# ASM2001.net
KiCad netlist of a schematic drawn in EAGLE
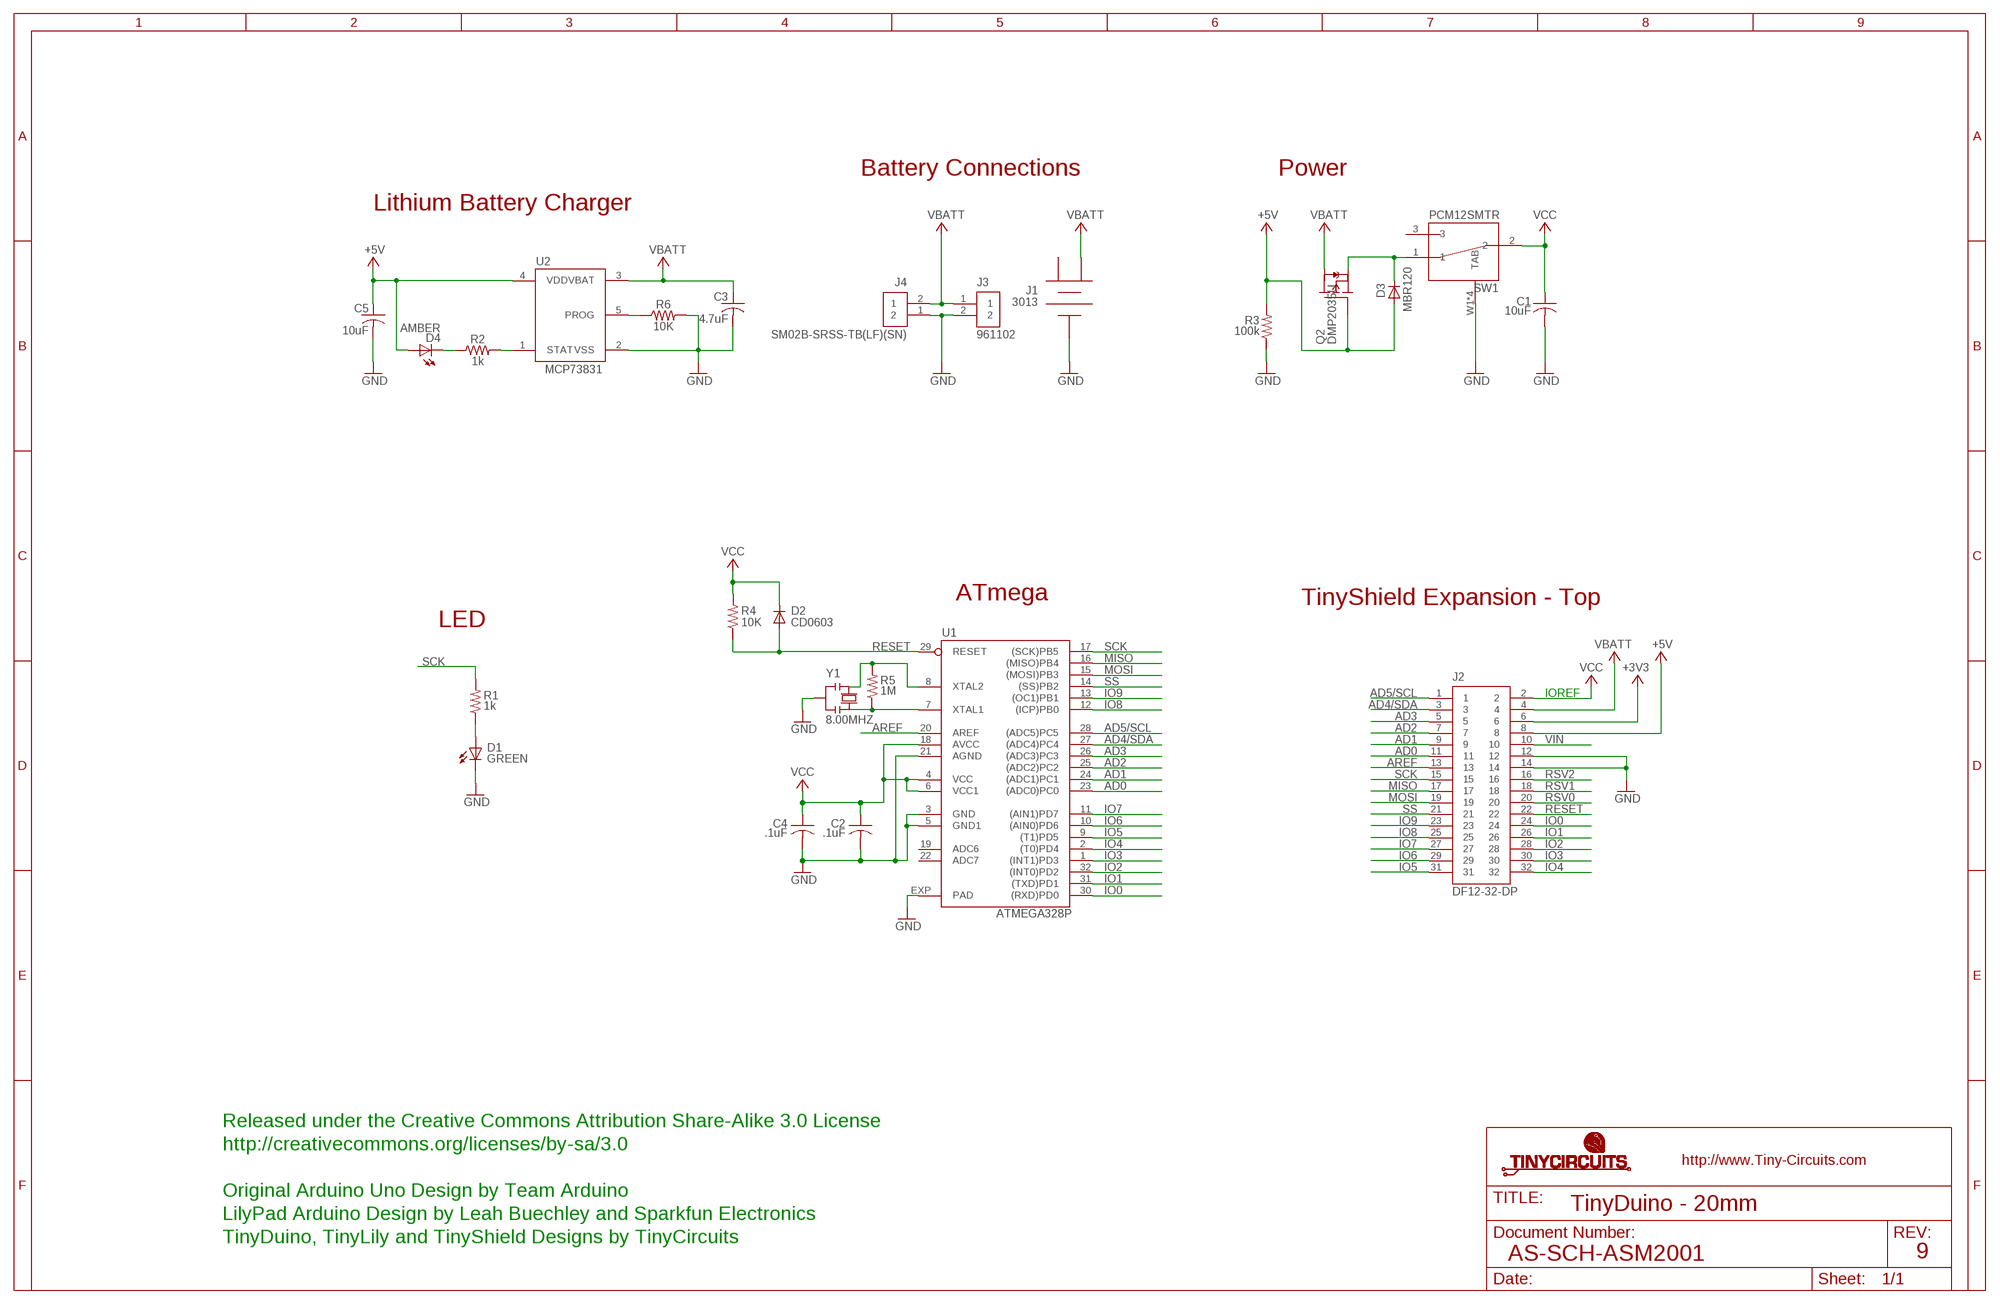
[diagram p0: schematic, sheet 1]

(export (version "E")
  (design (tool "Eeschema 10.0.6"))
  (components
    (comp (ref "C1")
      (value "10uF")
      (footprint "eagle-import:C0603")
      (fields (field (name "PARTNO") "AS-ITM-00002") (field (name "PARTNO_1") "AS-ITM-00002"))
      (libsource (lib "eagle-import") (part "AS-ITM-00002"))
    )
    (comp (ref "C2")
      (value ".1uF")
      (footprint "eagle-import:C0402")
      (fields (field (name "PARTNO") "AS-ITM-00008") (field (name "PARTNO_1") "AS-ITM-00008"))
      (libsource (lib "eagle-import") (part "AS-ITM-00008"))
    )
    (comp (ref "C3")
      (value "4.7uF")
      (footprint "eagle-import:C0402")
      (fields (field (name "PARTNO") "AS-ITM-00242") (field (name "PARTNO_1") "AS-ITM-00242"))
      (libsource (lib "eagle-import") (part "AS-ITM-00242"))
    )
    (comp (ref "C4")
      (value ".1uF")
      (footprint "eagle-import:C0402")
      (fields (field (name "PARTNO") "AS-ITM-00008") (field (name "PARTNO_1") "AS-ITM-00008"))
      (libsource (lib "eagle-import") (part "AS-ITM-00008"))
    )
    (comp (ref "C5")
      (value "10uF")
      (footprint "eagle-import:C0603")
      (fields (field (name "PARTNO") "AS-ITM-00002") (field (name "PARTNO_1") "AS-ITM-00002"))
      (libsource (lib "eagle-import") (part "AS-ITM-00002"))
    )
    (comp (ref "D1")
      (value "GREEN")
      (footprint "eagle-import:LNJ_LED")
      (fields (field (name "PARTNO") "AS-ITM-00011") (field (name "PARTNO_1") "AS-ITM-00011"))
      (libsource (lib "eagle-import") (part "AS-ITM-00011"))
    )
    (comp (ref "D2")
      (value "CD0603")
      (footprint "eagle-import:0603")
      (fields (field (name "PARTNO") "AS-ITM-00009") (field (name "PARTNO_1") "AS-ITM-00009"))
      (libsource (lib "eagle-import") (part "AS-ITM-00009"))
    )
    (comp (ref "D3")
      (value "MBR120")
      (footprint "eagle-import:SOD-123FL")
      (fields (field (name "PARTNO") "AS-ITM-00111"))
      (libsource (lib "eagle-import") (part "AS-ITM-00111"))
    )
    (comp (ref "D4")
      (value "AMBER")
      (footprint "eagle-import:LNJ_LED")
      (fields (field (name "PARTNO") "AS-ITM-00026") (field (name "PARTNO_1") "AS-ITM-00026"))
      (libsource (lib "eagle-import") (part "AS-ITM-00026"))
    )
    (comp (ref "J1")
      (value "3013")
      (footprint "eagle-import:3013")
      (fields (field (name "PARTNO") "AS-ITM-00001") (field (name "PARTNO_1") "AS-ITM-00001"))
      (libsource (lib "eagle-import") (part "AS-ITM-00001"))
    )
    (comp (ref "J2")
      (value "DF12-32-DP")
      (footprint "eagle-import:DF12-32-DP")
      (fields (field (name "PARTNO") "AS-ITM-00015") (field (name "PARTNO_1") "AS-ITM-00015"))
      (libsource (lib "eagle-import") (part "AS-ITM-00015"))
    )
    (comp (ref "J3")
      (value "961102")
      (footprint "eagle-import:2X.1_")
      (fields (field (name "PARTNO") "AS-ITM-00044"))
      (libsource (lib "eagle-import") (part "AS-ITM-00044"))
    )
    (comp (ref "J4")
      (value "SM02B-SRSS-TB(LF)(SN)")
      (footprint "eagle-import:JST_SH_2X1")
      (fields (field (name "PARTNO") "AS-ITM-00231"))
      (libsource (lib "eagle-import") (part "AS-ITM-00231"))
    )
    (comp (ref "Q2")
      (value "DMP2035U")
      (footprint "eagle-import:SOT23")
      (fields (field (name "PARTNO") "AS-ITM-00024"))
      (libsource (lib "eagle-import") (part "AS-ITM-00024"))
    )
    (comp (ref "R1")
      (value "1k")
      (footprint "eagle-import:0402")
      (fields (field (name "PARTNO") "AS-ITM-00003") (field (name "PARTNO_1") "AS-ITM-00003"))
      (libsource (lib "eagle-import") (part "AS-ITM-00003"))
    )
    (comp (ref "R2")
      (value "1k")
      (footprint "eagle-import:0402")
      (fields (field (name "PARTNO") "AS-ITM-00003") (field (name "PARTNO_1") "AS-ITM-00003"))
      (libsource (lib "eagle-import") (part "AS-ITM-00003"))
    )
    (comp (ref "R3")
      (value "100k")
      (footprint "eagle-import:0402")
      (fields (field (name "PARTNO") "AS-ITM-00004") (field (name "PARTNO_1") "AS-ITM-00004"))
      (libsource (lib "eagle-import") (part "AS-ITM-00004"))
    )
    (comp (ref "R4")
      (value "10K")
      (footprint "eagle-import:0402")
      (fields (field (name "PARTNO") "AS-ITM-00032") (field (name "PARTNO_1") "AS-ITM-00032"))
      (libsource (lib "eagle-import") (part "AS-ITM-00032"))
    )
    (comp (ref "R5")
      (value "1M")
      (footprint "eagle-import:0402")
      (fields (field (name "PARTNO") "AS-ITM-00005") (field (name "PARTNO_1") "AS-ITM-00005"))
      (libsource (lib "eagle-import") (part "AS-ITM-00005"))
    )
    (comp (ref "R6")
      (value "10K")
      (footprint "eagle-import:0402")
      (fields (field (name "PARTNO") "AS-ITM-00032"))
      (libsource (lib "eagle-import") (part "AS-ITM-00032"))
    )
    (comp (ref "SW1")
      (value "PCM12SMTR")
      (footprint "eagle-import:PCM12SMTR")
      (fields (field (name "PARTNO") "AS-ITM-00220"))
      (libsource (lib "eagle-import") (part "AS-ITM-00220"))
    )
    (comp (ref "U1")
      (value "ATMEGA328P")
      (footprint "eagle-import:ATMEL_QFN32")
      (fields (field (name "PARTNO") "AS-ITM-00013") (field (name "PARTNO_1") "AS-ITM-00013"))
      (libsource (lib "eagle-import") (part "AS-ITM-00013MU"))
    )
    (comp (ref "U2")
      (value "MCP73831")
      (footprint "eagle-import:SOT-23")
      (fields (field (name "PARTNO") "AS-ITM-00136"))
      (libsource (lib "eagle-import") (part "AS-ITM-00136"))
    )
    (comp (ref "Y1")
      (value "8.00MHZ")
      (footprint "eagle-import:RESONATOR_SMALL")
      (fields (field (name "PARTNO") "AS-ITM-0027") (field (name "PARTNO_1") "AS-ITM-00027"))
      (libsource (lib "eagle-import") (part "AS-ITM-00027B"))
    )
  )
  (nets
    (net (code "1") (name "+3V3") (class "Default")
      (node (ref "J2") (pin "6") (pinfunction "6_6") (pintype "bidirectional"))
    )
    (net (code "2") (name "+5V") (class "Default")
      (node (ref "C5") (pin "1") (pinfunction "1_1") (pintype "passive"))
      (node (ref "D3") (pin "A") (pinfunction "A_A") (pintype "passive"))
      (node (ref "D4") (pin "A") (pinfunction "A_A") (pintype "passive"))
      (node (ref "J2") (pin "8") (pinfunction "8_8") (pintype "bidirectional"))
      (node (ref "Q2") (pin "B") (pinfunction "G_B") (pintype "passive"))
      (node (ref "R3") (pin "2") (pinfunction "2_2") (pintype "passive"))
      (node (ref "U2") (pin "4") (pinfunction "VDD_4") (pintype "bidirectional"))
    )
    (net (code "3") (name "/1") (class "Default")
      (node (ref "J1") (pin "1") (pinfunction "1_1") (pintype "power_in"))
    )
    (net (code "4") (name "/AD0") (class "Default")
      (node (ref "J2") (pin "11") (pinfunction "11_11") (pintype "bidirectional"))
      (node (ref "U1") (pin "23") (pinfunction "(ADC0)PC0_23") (pintype "bidirectional"))
    )
    (net (code "5") (name "/AD1") (class "Default")
      (node (ref "J2") (pin "9") (pinfunction "9_9") (pintype "bidirectional"))
      (node (ref "U1") (pin "24") (pinfunction "(ADC1)PC1_24") (pintype "bidirectional"))
    )
    (net (code "6") (name "/AD2") (class "Default")
      (node (ref "J2") (pin "7") (pinfunction "7_7") (pintype "bidirectional"))
      (node (ref "U1") (pin "25") (pinfunction "(ADC2)PC2_25") (pintype "bidirectional"))
    )
    (net (code "7") (name "/AD3") (class "Default")
      (node (ref "J2") (pin "5") (pinfunction "5_5") (pintype "bidirectional"))
      (node (ref "U1") (pin "26") (pinfunction "(ADC3)PC3_26") (pintype "bidirectional"))
    )
    (net (code "8") (name "/AD4{slash}SDA") (class "Default")
      (node (ref "J2") (pin "3") (pinfunction "3_3") (pintype "bidirectional"))
      (node (ref "U1") (pin "27") (pinfunction "(ADC4)PC4_27") (pintype "bidirectional"))
    )
    (net (code "9") (name "/AD5{slash}SCL") (class "Default")
      (node (ref "J2") (pin "1") (pinfunction "1_1") (pintype "bidirectional"))
      (node (ref "U1") (pin "28") (pinfunction "(ADC5)PC5_28") (pintype "bidirectional"))
    )
    (net (code "10") (name "/AREF") (class "Default")
      (node (ref "J2") (pin "13") (pinfunction "13_13") (pintype "bidirectional"))
      (node (ref "U1") (pin "20") (pinfunction "AREF_20") (pintype "passive"))
    )
    (net (code "11") (name "/IO0") (class "Default")
      (node (ref "J2") (pin "24") (pinfunction "24_24") (pintype "bidirectional"))
      (node (ref "U1") (pin "30") (pinfunction "(RXD)PD0_30") (pintype "bidirectional"))
    )
    (net (code "12") (name "/IO1") (class "Default")
      (node (ref "J2") (pin "26") (pinfunction "26_26") (pintype "bidirectional"))
      (node (ref "U1") (pin "31") (pinfunction "(TXD)PD1_31") (pintype "bidirectional"))
    )
    (net (code "13") (name "/IO2") (class "Default")
      (node (ref "J2") (pin "28") (pinfunction "28_28") (pintype "bidirectional"))
      (node (ref "U1") (pin "32") (pinfunction "(INT0)PD2_32") (pintype "bidirectional"))
    )
    (net (code "14") (name "/IO3") (class "Default")
      (node (ref "J2") (pin "30") (pinfunction "30_30") (pintype "bidirectional"))
      (node (ref "U1") (pin "1") (pinfunction "(INT1)PD3_1") (pintype "bidirectional"))
    )
    (net (code "15") (name "/IO4") (class "Default")
      (node (ref "J2") (pin "32") (pinfunction "32_32") (pintype "bidirectional"))
      (node (ref "U1") (pin "2") (pinfunction "(T0)PD4_2") (pintype "bidirectional"))
    )
    (net (code "16") (name "/IO5") (class "Default")
      (node (ref "J2") (pin "31") (pinfunction "31_31") (pintype "bidirectional"))
      (node (ref "U1") (pin "9") (pinfunction "(T1)PD5_9") (pintype "bidirectional"))
    )
    (net (code "17") (name "/IO6") (class "Default")
      (node (ref "J2") (pin "29") (pinfunction "29_29") (pintype "bidirectional"))
      (node (ref "U1") (pin "10") (pinfunction "(AIN0)PD6_10") (pintype "bidirectional"))
    )
    (net (code "18") (name "/IO7") (class "Default")
      (node (ref "J2") (pin "27") (pinfunction "27_27") (pintype "bidirectional"))
      (node (ref "U1") (pin "11") (pinfunction "(AIN1)PD7_11") (pintype "bidirectional"))
    )
    (net (code "19") (name "/IO8") (class "Default")
      (node (ref "J2") (pin "25") (pinfunction "25_25") (pintype "bidirectional"))
      (node (ref "U1") (pin "12") (pinfunction "(ICP)PB0_12") (pintype "bidirectional"))
    )
    (net (code "20") (name "/IO9") (class "Default")
      (node (ref "J2") (pin "23") (pinfunction "23_23") (pintype "bidirectional"))
      (node (ref "U1") (pin "13") (pinfunction "(OC1)PB1_13") (pintype "bidirectional"))
    )
    (net (code "21") (name "/MISO") (class "Default")
      (node (ref "J2") (pin "17") (pinfunction "17_17") (pintype "bidirectional"))
      (node (ref "U1") (pin "16") (pinfunction "(MISO)PB4_16") (pintype "bidirectional"))
    )
    (net (code "22") (name "/MOSI") (class "Default")
      (node (ref "J2") (pin "19") (pinfunction "19_19") (pintype "bidirectional"))
      (node (ref "U1") (pin "15") (pinfunction "(MOSI)PB3_15") (pintype "bidirectional"))
    )
    (net (code "23") (name "/RESET") (class "Default")
      (node (ref "D2") (pin "A") (pinfunction "A_A") (pintype "passive"))
      (node (ref "J2") (pin "22") (pinfunction "22_22") (pintype "bidirectional"))
      (node (ref "R4") (pin "1") (pinfunction "1_1") (pintype "passive"))
      (node (ref "U1") (pin "29") (pinfunction "RESET_29") (pintype "input"))
    )
    (net (code "24") (name "/RSV0") (class "Default")
      (node (ref "J2") (pin "20") (pinfunction "20_20") (pintype "bidirectional"))
    )
    (net (code "25") (name "/RSV1") (class "Default")
      (node (ref "J2") (pin "18") (pinfunction "18_18") (pintype "bidirectional"))
    )
    (net (code "26") (name "/RSV2") (class "Default")
      (node (ref "J2") (pin "16") (pinfunction "16_16") (pintype "bidirectional"))
    )
    (net (code "27") (name "/SCK") (class "Default")
      (node (ref "J2") (pin "15") (pinfunction "15_15") (pintype "bidirectional"))
      (node (ref "R1") (pin "2") (pinfunction "2_2") (pintype "passive"))
      (node (ref "U1") (pin "17") (pinfunction "(SCK)PB5_17") (pintype "bidirectional"))
    )
    (net (code "28") (name "/SS") (class "Default")
      (node (ref "J2") (pin "21") (pinfunction "21_21") (pintype "bidirectional"))
      (node (ref "U1") (pin "14") (pinfunction "(SS)PB2_14") (pintype "bidirectional"))
    )
    (net (code "29") (name "/VIN") (class "Default")
      (node (ref "J2") (pin "10") (pinfunction "10_10") (pintype "bidirectional"))
    )
    (net (code "30") (name "GND") (class "Default")
      (node (ref "C1") (pin "2") (pinfunction "2_2") (pintype "passive"))
      (node (ref "C2") (pin "2") (pinfunction "2_2") (pintype "passive"))
      (node (ref "C3") (pin "2") (pinfunction "2_2") (pintype "passive"))
      (node (ref "C4") (pin "2") (pinfunction "2_2") (pintype "passive"))
      (node (ref "C5") (pin "2") (pinfunction "2_2") (pintype "passive"))
      (node (ref "D1") (pin "C") (pinfunction "C_C") (pintype "passive"))
      (node (ref "J1") (pin "3") (pinfunction "3_3") (pintype "power_in"))
      (node (ref "J2") (pin "12") (pinfunction "12_12") (pintype "bidirectional"))
      (node (ref "J2") (pin "14") (pinfunction "14_14") (pintype "bidirectional"))
      (node (ref "J3") (pin "2") (pinfunction "2_2") (pintype "bidirectional"))
      (node (ref "J4") (pin "1") (pinfunction "2_1") (pintype "bidirectional"))
      (node (ref "R3") (pin "1") (pinfunction "1_1") (pintype "passive"))
      (node (ref "R6") (pin "2") (pinfunction "2_2") (pintype "passive"))
      (node (ref "SW1") (pin "W1") (pinfunction "TAB_W1") (pintype "bidirectional"))
      (node (ref "SW1") (pin "W2") (pinfunction "TAB_W2") (pintype "bidirectional"))
      (node (ref "SW1") (pin "W3") (pinfunction "TAB_W3") (pintype "bidirectional"))
      (node (ref "SW1") (pin "W4") (pinfunction "TAB_W4") (pintype "bidirectional"))
      (node (ref "U1") (pin "21") (pinfunction "AGND_21") (pintype "power_in"))
      (node (ref "U1") (pin "3") (pinfunction "GND_3") (pintype "power_in"))
      (node (ref "U1") (pin "5") (pinfunction "GND1_5") (pintype "power_in"))
      (node (ref "U1") (pin "EXP") (pinfunction "PAD_EXP") (pintype "power_in"))
      (node (ref "U2") (pin "2") (pinfunction "VSS_2") (pintype "bidirectional"))
      (node (ref "Y1") (pin "2") (pinfunction "2_2") (pintype "passive"))
    )
    (net (code "31") (name "Net-(D1-PadA)") (class "Default")
      (node (ref "D1") (pin "A") (pinfunction "A_A") (pintype "passive"))
      (node (ref "R1") (pin "1") (pinfunction "1_1") (pintype "passive"))
    )
    (net (code "32") (name "Net-(D4-PadC)") (class "Default")
      (node (ref "D4") (pin "C") (pinfunction "C_C") (pintype "passive"))
      (node (ref "R2") (pin "1") (pinfunction "1_1") (pintype "passive"))
    )
    (net (code "33") (name "Net-(Q2-S)") (class "Default")
      (node (ref "D3") (pin "C") (pinfunction "C_C") (pintype "passive"))
      (node (ref "Q2") (pin "E") (pinfunction "S_E") (pintype "passive"))
      (node (ref "SW1") (pin "1") (pinfunction "1_1") (pintype "bidirectional"))
    )
    (net (code "34") (name "Net-(U1-XTAL1)") (class "Default")
      (node (ref "R5") (pin "1") (pinfunction "1_1") (pintype "passive"))
      (node (ref "U1") (pin "7") (pinfunction "XTAL1_7") (pintype "bidirectional"))
      (node (ref "Y1") (pin "3") (pinfunction "3_3") (pintype "passive"))
    )
    (net (code "35") (name "Net-(U1-XTAL2)") (class "Default")
      (node (ref "R5") (pin "2") (pinfunction "2_2") (pintype "passive"))
      (node (ref "U1") (pin "8") (pinfunction "XTAL2_8") (pintype "bidirectional"))
      (node (ref "Y1") (pin "1") (pinfunction "1_1") (pintype "passive"))
    )
    (net (code "36") (name "Net-(U2-PROG)") (class "Default")
      (node (ref "R6") (pin "1") (pinfunction "1_1") (pintype "passive"))
      (node (ref "U2") (pin "5") (pinfunction "PROG_5") (pintype "bidirectional"))
    )
    (net (code "37") (name "Net-(U2-STAT)") (class "Default")
      (node (ref "R2") (pin "2") (pinfunction "2_2") (pintype "passive"))
      (node (ref "U2") (pin "1") (pinfunction "STAT_1") (pintype "bidirectional"))
    )
    (net (code "38") (name "VBATT") (class "Default")
      (node (ref "C3") (pin "1") (pinfunction "1_1") (pintype "passive"))
      (node (ref "J1") (pin "2") (pinfunction "2_2") (pintype "power_in"))
      (node (ref "J2") (pin "4") (pinfunction "4_4") (pintype "bidirectional"))
      (node (ref "J3") (pin "1") (pinfunction "1_1") (pintype "bidirectional"))
      (node (ref "J4") (pin "2") (pinfunction "1_2") (pintype "bidirectional"))
      (node (ref "Q2") (pin "C") (pinfunction "D_C") (pintype "passive"))
      (node (ref "U2") (pin "3") (pinfunction "VBAT_3") (pintype "bidirectional"))
    )
    (net (code "39") (name "VCC") (class "Default")
      (node (ref "C1") (pin "1") (pinfunction "1_1") (pintype "passive"))
      (node (ref "C2") (pin "1") (pinfunction "1_1") (pintype "passive"))
      (node (ref "C4") (pin "1") (pinfunction "1_1") (pintype "passive"))
      (node (ref "D2") (pin "C") (pinfunction "C_C") (pintype "passive"))
      (node (ref "J2") (pin "2") (pinfunction "2_2") (pintype "bidirectional"))
      (node (ref "R4") (pin "2") (pinfunction "2_2") (pintype "passive"))
      (node (ref "SW1") (pin "2") (pinfunction "2_2") (pintype "bidirectional"))
      (node (ref "U1") (pin "18") (pinfunction "AVCC_18") (pintype "power_in"))
      (node (ref "U1") (pin "4") (pinfunction "VCC_4") (pintype "power_in"))
      (node (ref "U1") (pin "6") (pinfunction "VCC1_6") (pintype "power_in"))
    )
    (net (code "40") (name "unconnected-(SW1-Pad3)") (class "Default")
      (node (ref "SW1") (pin "3") (pinfunction "3_3") (pintype "bidirectional"))
    )
    (net (code "41") (name "unconnected-(U1-ADC6-Pad19)") (class "Default")
      (node (ref "U1") (pin "19") (pinfunction "ADC6_19") (pintype "bidirectional"))
    )
    (net (code "42") (name "unconnected-(U1-ADC7-Pad22)") (class "Default")
      (node (ref "U1") (pin "22") (pinfunction "ADC7_22") (pintype "bidirectional"))
    )
  )
)
